# tinyTorch.net
KiCad netlist of a schematic drawn in EAGLE
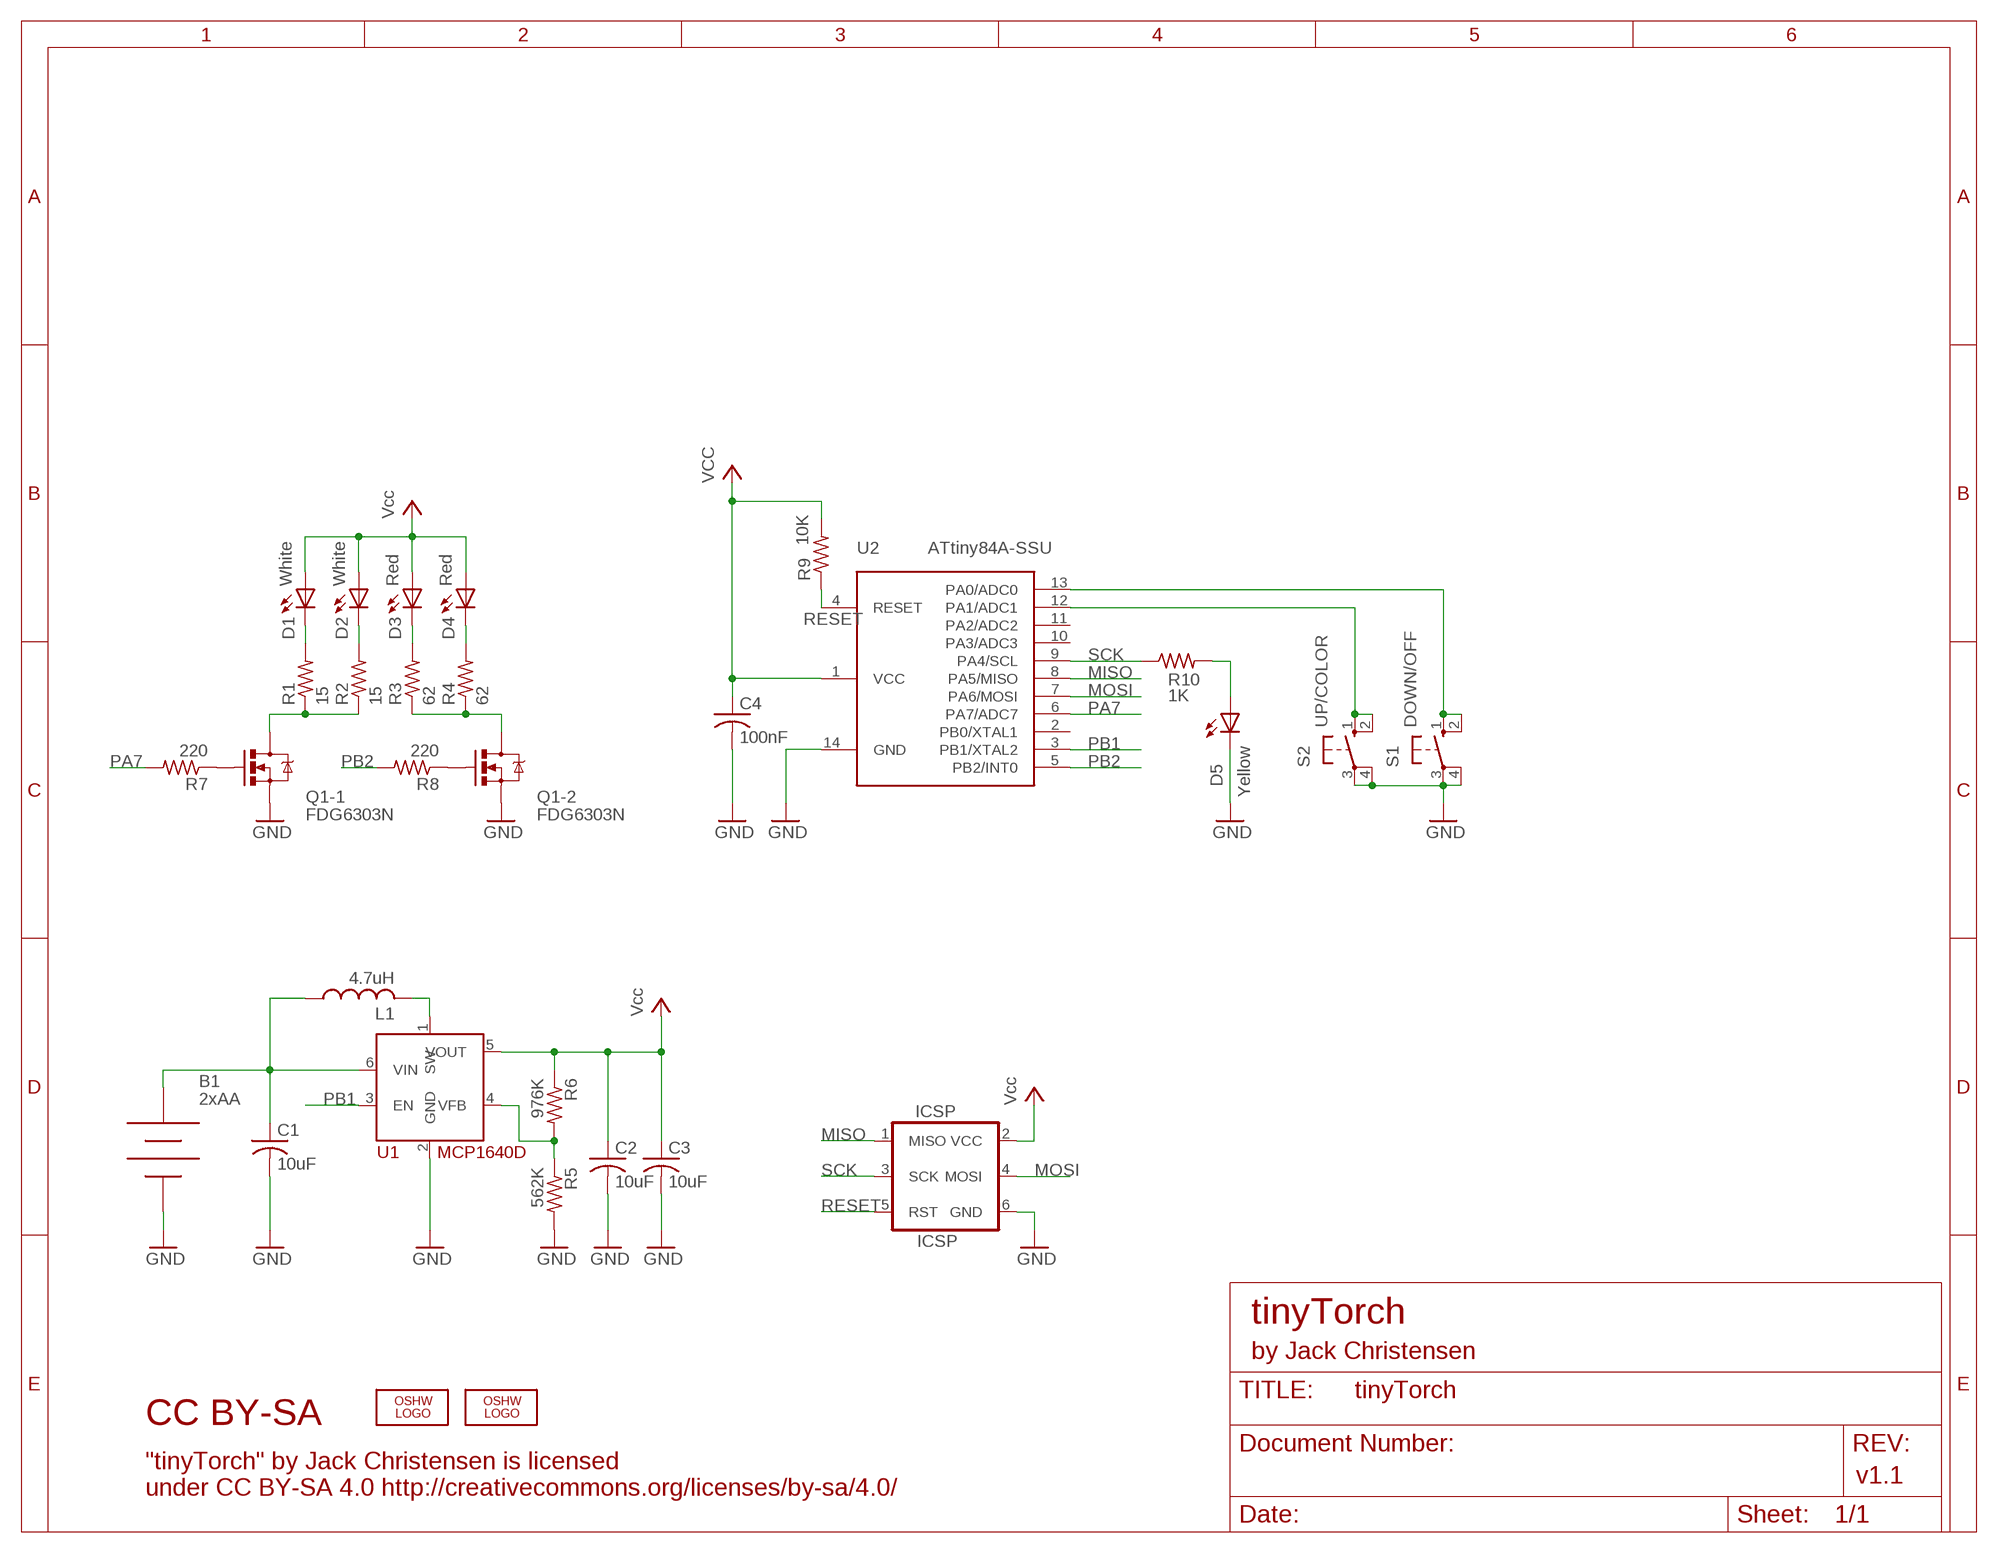
[diagram p0: schematic, sheet 1]

(export (version "E")
  (design (tool "Eeschema 10.0.6"))
  (components
    (comp (ref "B1")
      (value "2xAA")
      (footprint "eagle-import:KEYSTONE-2462-NO-HOLES")
      (fields (field (name "MFR") "Keystone"))
      (libsource (lib "eagle-import") (part "BATTERY-2AANOHOLES"))
    )
    (comp (ref "C1")
      (value "10uF")
      (footprint "eagle-import:M0805")
      (libsource (lib "eagle-import") (part "C-USM0805"))
    )
    (comp (ref "C2")
      (value "10uF")
      (footprint "eagle-import:M0805")
      (libsource (lib "eagle-import") (part "C-USM0805"))
    )
    (comp (ref "C3")
      (value "10uF")
      (footprint "eagle-import:M0805")
      (libsource (lib "eagle-import") (part "C-USM0805"))
    )
    (comp (ref "C4")
      (value "100nF")
      (footprint "eagle-import:M0805")
      (libsource (lib "eagle-import") (part "C-USM0805"))
    )
    (comp (ref "D1")
      (value "White")
      (footprint "eagle-import:LED5MM-OVAL")
      (fields (field (name "MFR") "Cree"))
      (libsource (lib "eagle-import") (part "LED5MM-LONGPADS"))
    )
    (comp (ref "D2")
      (value "White")
      (footprint "eagle-import:LED5MM-OVAL")
      (fields (field (name "MFR") "Cree"))
      (libsource (lib "eagle-import") (part "LED5MM-LONGPADS"))
    )
    (comp (ref "D3")
      (value "Red")
      (footprint "eagle-import:LED5MM-OVAL")
      (fields (field (name "MFR") "Lite-On"))
      (libsource (lib "eagle-import") (part "LED5MM-LONGPADS"))
    )
    (comp (ref "D4")
      (value "Red")
      (footprint "eagle-import:LED5MM-OVAL")
      (fields (field (name "MFR") "Lite-On"))
      (libsource (lib "eagle-import") (part "LED5MM-LONGPADS"))
    )
    (comp (ref "D5")
      (value "Yellow")
      (footprint "eagle-import:D0805A")
      (fields (field (name "MFR") "Lite-On"))
      (libsource (lib "eagle-import") (part "LEDD0805A"))
    )
    (comp (ref "ICSP")
      (value "ICSP")
      (footprint "eagle-import:2X3_LOCK")
      (libsource (lib "eagle-import") (part "AVR_SPI_PRG_62X3_LOCK"))
    )
    (comp (ref "L1")
      (value "4.7uH")
      (footprint "eagle-import:C1210K")
      (fields (field (name "MFR") "Taiyo Yuden"))
      (libsource (lib "eagle-import") (part "INDUCTORC1210K"))
    )
    (comp (ref "LOGO1")
      (value "OSHW_LOGO_8MILX0150-NT")
      (footprint "eagle-import:OSHW_8X150_NOTEXT")
      (libsource (lib "eagle-import") (part "OSHW_LOGO_8MILX0150-NT"))
    )
    (comp (ref "LOGO2")
      (value "OSHW_LOGO_10MILX0200-NT")
      (footprint "eagle-import:OSHW_10X200_NOTEXT")
      (libsource (lib "eagle-import") (part "OSHW_LOGO_10MILX0200-NT"))
    )
    (comp (ref "Q1")
      (value "FDG6303N")
      (footprint "eagle-import:SOT363_PHILIPS")
      (libsource (lib "eagle-import") (part "DUAL-MOSFET"))
    )
    (comp (ref "R1")
      (value "15")
      (footprint "eagle-import:M0805")
      (libsource (lib "eagle-import") (part "R-US_M0805"))
    )
    (comp (ref "R2")
      (value "15")
      (footprint "eagle-import:M0805")
      (libsource (lib "eagle-import") (part "R-US_M0805"))
    )
    (comp (ref "R3")
      (value "62")
      (footprint "eagle-import:M0805")
      (libsource (lib "eagle-import") (part "R-US_M0805"))
    )
    (comp (ref "R4")
      (value "62")
      (footprint "eagle-import:M0805")
      (libsource (lib "eagle-import") (part "R-US_M0805"))
    )
    (comp (ref "R5")
      (value "562K")
      (footprint "eagle-import:M0805")
      (libsource (lib "eagle-import") (part "R-US_M0805"))
    )
    (comp (ref "R6")
      (value "976K")
      (footprint "eagle-import:M0805")
      (libsource (lib "eagle-import") (part "R-US_M0805"))
    )
    (comp (ref "R7")
      (value "220")
      (footprint "eagle-import:M0805")
      (libsource (lib "eagle-import") (part "R-US_M0805"))
    )
    (comp (ref "R8")
      (value "220")
      (footprint "eagle-import:M0805")
      (libsource (lib "eagle-import") (part "R-US_M0805"))
    )
    (comp (ref "R9")
      (value "10K")
      (footprint "eagle-import:M0805")
      (libsource (lib "eagle-import") (part "R-US_M0805"))
    )
    (comp (ref "R10")
      (value "1K")
      (footprint "eagle-import:M0805")
      (libsource (lib "eagle-import") (part "R-US_M0805"))
    )
    (comp (ref "S1")
      (value "DOWN/OFF")
      (footprint "eagle-import:TACT-SW-SMT")
      (fields (field (name "MFR") "Omron"))
      (libsource (lib "eagle-import") (part "10-XXSMT"))
    )
    (comp (ref "S2")
      (value "UP/COLOR")
      (footprint "eagle-import:TACT-SW-SMT")
      (fields (field (name "MFR") "Omron"))
      (libsource (lib "eagle-import") (part "10-XXSMT"))
    )
    (comp (ref "U1")
      (value "MCP1640D")
      (footprint "eagle-import:SOT23-6")
      (libsource (lib "eagle-import") (part "MCP1640"))
    )
    (comp (ref "U2")
      (value "ATtiny84A-SSU")
      (footprint "eagle-import:SO14")
      (libsource (lib "eagle-import") (part "ATTINYX4SO14"))
    )
  )
  (nets
    (net (code "1") (name "/MISO") (class "Default")
      (node (ref "ICSP") (pin "1") (pinfunction "MISO_1") (pintype "passive"))
      (node (ref "U2") (pin "8") (pinfunction "PA5/MISO_8") (pintype "bidirectional"))
    )
    (net (code "2") (name "/MOSI") (class "Default")
      (node (ref "ICSP") (pin "4") (pinfunction "MOSI_4") (pintype "passive"))
      (node (ref "U2") (pin "7") (pinfunction "PA6/MOSI_7") (pintype "bidirectional"))
    )
    (net (code "3") (name "/PA7") (class "Default")
      (node (ref "R7") (pin "2") (pinfunction "2_2") (pintype "passive"))
      (node (ref "U2") (pin "6") (pinfunction "PA7/ADC7_6") (pintype "bidirectional"))
    )
    (net (code "4") (name "/PB1") (class "Default")
      (node (ref "U1") (pin "3") (pinfunction "EN_3") (pintype "passive"))
      (node (ref "U2") (pin "3") (pinfunction "PB1/XTAL2_3") (pintype "bidirectional"))
    )
    (net (code "5") (name "/PB2") (class "Default")
      (node (ref "R8") (pin "2") (pinfunction "2_2") (pintype "passive"))
      (node (ref "U2") (pin "5") (pinfunction "PB2/INT0_5") (pintype "bidirectional"))
    )
    (net (code "6") (name "/RESET") (class "Default")
      (node (ref "ICSP") (pin "5") (pinfunction "RST_5") (pintype "passive"))
      (node (ref "R9") (pin "1") (pinfunction "1_1") (pintype "passive"))
      (node (ref "U2") (pin "4") (pinfunction "RESET_4") (pintype "bidirectional"))
    )
    (net (code "7") (name "/SCK") (class "Default")
      (node (ref "ICSP") (pin "3") (pinfunction "SCK_3") (pintype "passive"))
      (node (ref "R10") (pin "1") (pinfunction "1_1") (pintype "passive"))
      (node (ref "U2") (pin "9") (pinfunction "PA4/SCL_9") (pintype "bidirectional"))
    )
    (net (code "8") (name "GND") (class "Default")
      (node (ref "B1") (pin "NEG") (pinfunction "NEG_NEG") (pintype "bidirectional"))
      (node (ref "C1") (pin "2") (pinfunction "2_2") (pintype "passive"))
      (node (ref "C2") (pin "2") (pinfunction "2_2") (pintype "passive"))
      (node (ref "C3") (pin "2") (pinfunction "2_2") (pintype "passive"))
      (node (ref "C4") (pin "2") (pinfunction "2_2") (pintype "passive"))
      (node (ref "D5") (pin "K") (pinfunction "C_K") (pintype "passive"))
      (node (ref "ICSP") (pin "6") (pinfunction "GND_6") (pintype "passive"))
      (node (ref "Q1") (pin "1") (pinfunction "S_1") (pintype "passive"))
      (node (ref "Q1") (pin "4") (pinfunction "S_4") (pintype "passive"))
      (node (ref "R5") (pin "2") (pinfunction "2_2") (pintype "passive"))
      (node (ref "S1") (pin "3") (pinfunction "P_3") (pintype "passive"))
      (node (ref "S1") (pin "4") (pinfunction "P1_4") (pintype "passive"))
      (node (ref "S2") (pin "3") (pinfunction "P_3") (pintype "passive"))
      (node (ref "S2") (pin "4") (pinfunction "P1_4") (pintype "passive"))
      (node (ref "U1") (pin "2") (pinfunction "GND_2") (pintype "passive"))
      (node (ref "U2") (pin "14") (pinfunction "GND_14") (pintype "bidirectional"))
    )
    (net (code "9") (name "Net-(D1-C)") (class "Default")
      (node (ref "D1") (pin "K") (pinfunction "C_K") (pintype "passive"))
      (node (ref "R1") (pin "2") (pinfunction "2_2") (pintype "passive"))
    )
    (net (code "10") (name "Net-(D2-C)") (class "Default")
      (node (ref "D2") (pin "K") (pinfunction "C_K") (pintype "passive"))
      (node (ref "R2") (pin "2") (pinfunction "2_2") (pintype "passive"))
    )
    (net (code "11") (name "Net-(D3-C)") (class "Default")
      (node (ref "D3") (pin "K") (pinfunction "C_K") (pintype "passive"))
      (node (ref "R3") (pin "2") (pinfunction "2_2") (pintype "passive"))
    )
    (net (code "12") (name "Net-(D4-C)") (class "Default")
      (node (ref "D4") (pin "K") (pinfunction "C_K") (pintype "passive"))
      (node (ref "R4") (pin "2") (pinfunction "2_2") (pintype "passive"))
    )
    (net (code "13") (name "Net-(D5-PadA)") (class "Default")
      (node (ref "D5") (pin "A") (pinfunction "A_A") (pintype "passive"))
      (node (ref "R10") (pin "2") (pinfunction "2_2") (pintype "passive"))
    )
    (net (code "14") (name "Net-(Q1A-D)") (class "Default")
      (node (ref "Q1") (pin "6") (pinfunction "D_6") (pintype "passive"))
      (node (ref "R1") (pin "1") (pinfunction "1_1") (pintype "passive"))
      (node (ref "R2") (pin "1") (pinfunction "1_1") (pintype "passive"))
    )
    (net (code "15") (name "Net-(Q1A-G)") (class "Default")
      (node (ref "Q1") (pin "2") (pinfunction "G_2") (pintype "passive"))
      (node (ref "R7") (pin "1") (pinfunction "1_1") (pintype "passive"))
    )
    (net (code "16") (name "Net-(Q1B-D)") (class "Default")
      (node (ref "Q1") (pin "3") (pinfunction "D_3") (pintype "passive"))
      (node (ref "R3") (pin "1") (pinfunction "1_1") (pintype "passive"))
      (node (ref "R4") (pin "1") (pinfunction "1_1") (pintype "passive"))
    )
    (net (code "17") (name "Net-(Q1B-G)") (class "Default")
      (node (ref "Q1") (pin "5") (pinfunction "G_5") (pintype "passive"))
      (node (ref "R8") (pin "1") (pinfunction "1_1") (pintype "passive"))
    )
    (net (code "18") (name "Net-(S1-S)") (class "Default")
      (node (ref "S1") (pin "1") (pinfunction "S_1") (pintype "passive"))
      (node (ref "S1") (pin "2") (pinfunction "S1_2") (pintype "passive"))
      (node (ref "U2") (pin "13") (pinfunction "PA0/ADC0_13") (pintype "bidirectional"))
    )
    (net (code "19") (name "Net-(S2-S)") (class "Default")
      (node (ref "S2") (pin "1") (pinfunction "S_1") (pintype "passive"))
      (node (ref "S2") (pin "2") (pinfunction "S1_2") (pintype "passive"))
      (node (ref "U2") (pin "12") (pinfunction "PA1/ADC1_12") (pintype "bidirectional"))
    )
    (net (code "20") (name "Net-(U1-SW)") (class "Default")
      (node (ref "L1") (pin "2") (pinfunction "2_2") (pintype "passive"))
      (node (ref "U1") (pin "1") (pinfunction "SW_1") (pintype "passive"))
    )
    (net (code "21") (name "Net-(U1-VFB)") (class "Default")
      (node (ref "R5") (pin "1") (pinfunction "1_1") (pintype "passive"))
      (node (ref "R6") (pin "2") (pinfunction "2_2") (pintype "passive"))
      (node (ref "U1") (pin "4") (pinfunction "VFB_4") (pintype "passive"))
    )
    (net (code "22") (name "Net-(U1-VIN)") (class "Default")
      (node (ref "B1") (pin "POS") (pinfunction "POS_POS") (pintype "bidirectional"))
      (node (ref "C1") (pin "1") (pinfunction "1_1") (pintype "passive"))
      (node (ref "L1") (pin "1") (pinfunction "1_1") (pintype "passive"))
      (node (ref "U1") (pin "6") (pinfunction "VIN_6") (pintype "passive"))
    )
    (net (code "23") (name "VCC") (class "Default")
      (node (ref "C2") (pin "1") (pinfunction "1_1") (pintype "passive"))
      (node (ref "C3") (pin "1") (pinfunction "1_1") (pintype "passive"))
      (node (ref "C4") (pin "1") (pinfunction "1_1") (pintype "passive"))
      (node (ref "D1") (pin "A") (pinfunction "A_A") (pintype "passive"))
      (node (ref "D2") (pin "A") (pinfunction "A_A") (pintype "passive"))
      (node (ref "D3") (pin "A") (pinfunction "A_A") (pintype "passive"))
      (node (ref "D4") (pin "A") (pinfunction "A_A") (pintype "passive"))
      (node (ref "ICSP") (pin "2") (pinfunction "VCC_2") (pintype "passive"))
      (node (ref "R6") (pin "1") (pinfunction "1_1") (pintype "passive"))
      (node (ref "R9") (pin "2") (pinfunction "2_2") (pintype "passive"))
      (node (ref "U1") (pin "5") (pinfunction "VOUT_5") (pintype "passive"))
      (node (ref "U2") (pin "1") (pinfunction "VCC_1") (pintype "bidirectional"))
    )
    (net (code "24") (name "unconnected-(U2-PA2{slash}ADC2-Pad11)") (class "Default")
      (node (ref "U2") (pin "11") (pinfunction "PA2/ADC2_11") (pintype "bidirectional"))
    )
    (net (code "25") (name "unconnected-(U2-PA3{slash}ADC3-Pad10)") (class "Default")
      (node (ref "U2") (pin "10") (pinfunction "PA3/ADC3_10") (pintype "bidirectional"))
    )
    (net (code "26") (name "unconnected-(U2-PB0{slash}XTAL1-Pad2)") (class "Default")
      (node (ref "U2") (pin "2") (pinfunction "PB0/XTAL1_2") (pintype "bidirectional"))
    )
  )
)
